# v1_0.net
KiCad netlist of a schematic drawn in Altium Designer
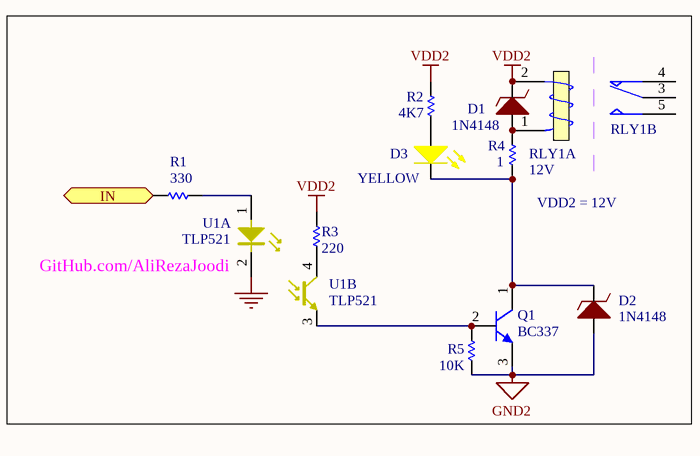
[diagram p0: v1.0.SchDoc]

(export (version "E")
  (design (tool "Eeschema 10.0.6"))
  (components
    (comp (ref "D1")
      (value "1N4148")
      (footprint "D_THD_AXIAL0.3_DO-35")
      (description "Diode, Zener")
      (libsource (lib "Passive") (part "Diode_Zener"))
    )
    (comp (ref "D2")
      (value "1N4148")
      (footprint "D_THD_AXIAL0.3_DO-35")
      (description "Diode, Zener")
      (libsource (lib "Passive") (part "Diode_Zener"))
    )
    (comp (ref "D3")
      (value "YELLOW")
      (footprint "LED_THD_3MM_YELLOW_R")
      (description "LED, Yellow")
      (fields (field (name "MANUFACTURER") "Generic Components") (field (name "PUBLISHER") "Altium Limited"))
      (libsource (lib "Display") (part "LED_YELLOW"))
    )
    (comp (ref "Q1")
      (value "BC337")
      (footprint "TO92C")
      (description "NPN Bipolar Transistor")
      (fields (field (name "MANUFACTURER") "Generic Components") (field (name "PUBLISHER") "Altium Limited"))
      (libsource (lib "Miscellaneous Devices") (part "NPN"))
    )
    (comp (ref "R1")
      (value "330")
      (footprint "R_THD_AXIAL0.4(1/4W)")
      (description "Resistor")
      (libsource (lib "Passive") (part "Resistor"))
    )
    (comp (ref "R2")
      (value "4K7")
      (footprint "R_THD_AXIAL0.4(1/4W)")
      (description "Resistor")
      (libsource (lib "Passive") (part "Resistor"))
    )
    (comp (ref "R3")
      (value "220")
      (footprint "R_THD_AXIAL0.4(1/4W)")
      (description "Resistor")
      (libsource (lib "Passive") (part "Resistor"))
    )
    (comp (ref "R4")
      (value "1")
      (footprint "R_THD_AXIAL0.4(1/4W)")
      (description "Resistor")
      (libsource (lib "Passive") (part "Resistor"))
    )
    (comp (ref "R5")
      (value "10K")
      (footprint "R_THD_AXIAL0.4(1/4W)")
      (description "Resistor")
      (libsource (lib "Passive") (part "Resistor"))
    )
    (comp (ref "RLY1")
      (value "12V")
      (footprint "RELAY_SPDT_5PIN_2216")
      (description "SPDT Relay")
      (libsource (lib "Passive") (part "Relay_SPDT_2Form"))
    )
    (comp (ref "U1")
      (value "TLP521")
      (footprint "DIP_4")
      (description "Optoisolator")
      (fields (field (name "PUBLISHER") "Altium Limited"))
      (libsource (lib "IC") (part "Optoisolator"))
    )
  )
  (nets
    (net (code "1") (name "/IN") (class "Default")
      (node (ref "R1") (pin "2") (pinfunction "2_2") (pintype "passive"))
    )
    (net (code "2") (name "GND") (class "Default")
      (node (ref "U1") (pin "2") (pinfunction "K_2") (pintype "power_in"))
    )
    (net (code "3") (name "GND2") (class "Default")
      (node (ref "D2") (pin "1") (pinfunction "1_1") (pintype "passive"))
      (node (ref "Q1") (pin "3") (pinfunction "E_3") (pintype "passive"))
      (node (ref "R5") (pin "2") (pinfunction "2_2") (pintype "passive"))
    )
    (net (code "4") (name "Net-(D3-A)") (class "Default")
      (node (ref "D3") (pin "1") (pinfunction "A_1") (pintype "passive"))
      (node (ref "R2") (pin "1") (pinfunction "1_1") (pintype "passive"))
    )
    (net (code "5") (name "Net-(D3-K)") (class "Default")
      (node (ref "D2") (pin "2") (pinfunction "2_2") (pintype "passive"))
      (node (ref "D3") (pin "2") (pinfunction "K_2") (pintype "passive"))
      (node (ref "Q1") (pin "1") (pinfunction "C_1") (pintype "passive"))
      (node (ref "R4") (pin "1") (pinfunction "1_1") (pintype "passive"))
    )
    (net (code "6") (name "Net-(Q1-B)") (class "Default")
      (node (ref "Q1") (pin "2") (pinfunction "B_2") (pintype "passive"))
      (node (ref "R5") (pin "1") (pinfunction "1_1") (pintype "passive"))
      (node (ref "U1") (pin "3") (pinfunction "E_3") (pintype "passive"))
    )
    (net (code "7") (name "Net-(RLY1A-T2)") (class "Default")
      (node (ref "D1") (pin "1") (pinfunction "1_1") (pintype "passive"))
      (node (ref "R4") (pin "2") (pinfunction "2_2") (pintype "passive"))
      (node (ref "RLY1") (pin "1") (pinfunction "T2_1") (pintype "passive"))
    )
    (net (code "8") (name "Net-(U1A-A)") (class "Default")
      (node (ref "R1") (pin "1") (pinfunction "1_1") (pintype "passive"))
      (node (ref "U1") (pin "1") (pinfunction "A_1") (pintype "power_in"))
    )
    (net (code "9") (name "Net-(U1B-C)") (class "Default")
      (node (ref "R3") (pin "2") (pinfunction "2_2") (pintype "passive"))
      (node (ref "U1") (pin "4") (pinfunction "C_4") (pintype "passive"))
    )
    (net (code "10") (name "VDD2") (class "Default")
      (node (ref "D1") (pin "2") (pinfunction "2_2") (pintype "passive"))
      (node (ref "R2") (pin "2") (pinfunction "2_2") (pintype "passive"))
      (node (ref "R3") (pin "1") (pinfunction "1_1") (pintype "passive"))
      (node (ref "RLY1") (pin "2") (pinfunction "T1_2") (pintype "passive"))
    )
    (net (code "11") (name "unconnected-(RLY1B-COM-Pad3)") (class "Default")
      (node (ref "RLY1") (pin "3") (pinfunction "COM_3") (pintype "passive"))
    )
    (net (code "12") (name "unconnected-(RLY1B-NC-Pad4)") (class "Default")
      (node (ref "RLY1") (pin "4") (pinfunction "NC_4") (pintype "passive"))
    )
    (net (code "13") (name "unconnected-(RLY1B-NO-Pad5)") (class "Default")
      (node (ref "RLY1") (pin "5") (pinfunction "NO_5") (pintype "passive"))
    )
  )
)
